# isense_rev1.net
KiCad netlist of a schematic drawn in EAGLE
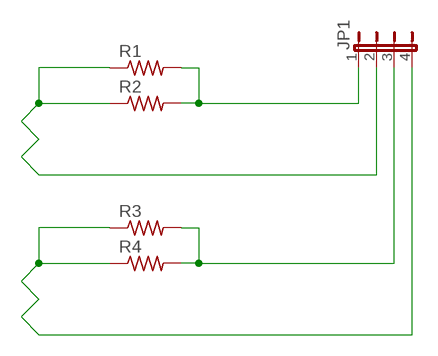
[diagram p0: schematic, sheet 1]

(export (version "E")
  (design (tool "Eeschema 10.0.6"))
  (components
    (comp (ref "JP1")
      (value "JP4E")
      (footprint "eagle-import:JP4")
      (libsource (lib "eagle-import") (part "JP4E"))
    )
    (comp (ref "R1")
      (value "R-US_R0603")
      (footprint "eagle-import:R0603")
      (libsource (lib "eagle-import") (part "R-US_R0603"))
    )
    (comp (ref "R2")
      (value "R-US_R0603")
      (footprint "eagle-import:R0603")
      (libsource (lib "eagle-import") (part "R-US_R0603"))
    )
    (comp (ref "R3")
      (value "R-US_R0603")
      (footprint "eagle-import:R0603")
      (libsource (lib "eagle-import") (part "R-US_R0603"))
    )
    (comp (ref "R4")
      (value "R-US_R0603")
      (footprint "eagle-import:R0603")
      (libsource (lib "eagle-import") (part "R-US_R0603"))
    )
  )
  (nets
    (net (code "1") (name "Net-(JP1-Pad1)") (class "Default")
      (node (ref "JP1") (pin "1") (pinfunction "1_1") (pintype "passive"))
      (node (ref "R1") (pin "2") (pinfunction "2_2") (pintype "passive"))
      (node (ref "R2") (pin "2") (pinfunction "2_2") (pintype "passive"))
    )
    (net (code "2") (name "Net-(JP1-Pad2)") (class "Default")
      (node (ref "JP1") (pin "2") (pinfunction "2_2") (pintype "passive"))
      (node (ref "R1") (pin "1") (pinfunction "1_1") (pintype "passive"))
      (node (ref "R2") (pin "1") (pinfunction "1_1") (pintype "passive"))
    )
    (net (code "3") (name "Net-(JP1-Pad3)") (class "Default")
      (node (ref "JP1") (pin "3") (pinfunction "3_3") (pintype "passive"))
      (node (ref "R3") (pin "2") (pinfunction "2_2") (pintype "passive"))
      (node (ref "R4") (pin "2") (pinfunction "2_2") (pintype "passive"))
    )
    (net (code "4") (name "Net-(JP1-Pad4)") (class "Default")
      (node (ref "JP1") (pin "4") (pinfunction "4_4") (pintype "passive"))
      (node (ref "R3") (pin "1") (pinfunction "1_1") (pintype "passive"))
      (node (ref "R4") (pin "1") (pinfunction "1_1") (pintype "passive"))
    )
  )
)
